# ATtiny10Thermometer.net
KiCad netlist of a schematic drawn in EAGLE
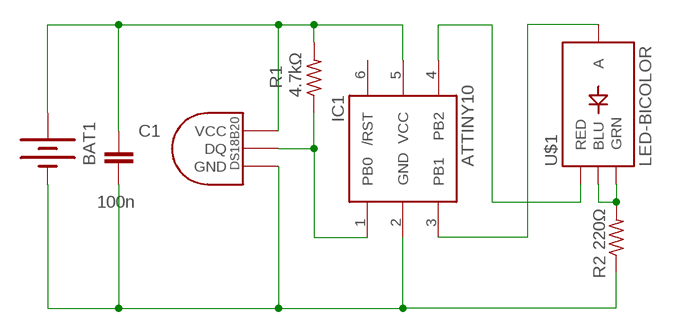
[diagram p0: schematic, sheet 1]

(export (version "E")
  (design (tool "Eeschema 10.0.6"))
  (components
    (comp (ref "BAT1")
      (value "BATTERY12MM")
      (footprint "eagle-import:BATTCON_12MM")
      (libsource (lib "eagle-import") (part "BATTERY12MM"))
    )
    (comp (ref "C1")
      (value "100n")
      (footprint "eagle-import:0603-CAP")
      (libsource (lib "eagle-import") (part "CAP0603-CAP"))
    )
    (comp (ref "IC1")
      (value "ATTINY10")
      (footprint "eagle-import:SOT23-6")
      (libsource (lib "eagle-import") (part "ATTINY10"))
    )
    (comp (ref "R1")
      (value "4.7kΩ")
      (footprint "eagle-import:R0805")
      (libsource (lib "eagle-import") (part "R-US_R0805"))
    )
    (comp (ref "R2")
      (value "220Ω")
      (footprint "eagle-import:R0805")
      (libsource (lib "eagle-import") (part "R-US_R0805"))
    )
    (comp (ref "U$1")
      (value "LED-BICOLOR")
      (footprint "eagle-import:LED-TRICOLOR-SMD")
      (libsource (lib "eagle-import") (part "LED-TRICOLOR"))
    )
    (comp (ref "U$2")
      (value "DS1820")
      (footprint "eagle-import:µSOP8")
      (libsource (lib "eagle-import") (part "DS1820"))
    )
  )
  (nets
    (net (code "1") (name "Net-(BAT1-+)") (class "Default")
      (node (ref "BAT1") (pin "PWR@1") (pinfunction "+_PWR@1") (pintype "power_in"))
      (node (ref "C1") (pin "1") (pinfunction "1_1") (pintype "passive"))
      (node (ref "IC1") (pin "5") (pinfunction "VCC_5") (pintype "power_in"))
      (node (ref "R1") (pin "2") (pinfunction "2_2") (pintype "passive"))
      (node (ref "U$2") (pin "8") (pinfunction "VCC_8") (pintype "power_in"))
    )
    (net (code "2") (name "Net-(BAT1--)") (class "Default")
      (node (ref "BAT1") (pin "GND") (pinfunction "-_GND") (pintype "power_in"))
      (node (ref "C1") (pin "2") (pinfunction "2_2") (pintype "passive"))
      (node (ref "IC1") (pin "2") (pinfunction "GND_2") (pintype "power_in"))
      (node (ref "R2") (pin "1") (pinfunction "1_1") (pintype "passive"))
      (node (ref "U$2") (pin "4") (pinfunction "GND_4") (pintype "power_in"))
    )
    (net (code "3") (name "Net-(IC1-PB0)") (class "Default")
      (node (ref "IC1") (pin "1") (pinfunction "PB0_1") (pintype "bidirectional"))
      (node (ref "R1") (pin "1") (pinfunction "1_1") (pintype "passive"))
      (node (ref "U$2") (pin "1") (pinfunction "DQ_1") (pintype "bidirectional"))
    )
    (net (code "4") (name "Net-(IC1-PB1)") (class "Default")
      (node (ref "IC1") (pin "3") (pinfunction "PB1_3") (pintype "bidirectional"))
      (node (ref "U$1") (pin "A") (pinfunction "A_A") (pintype "bidirectional"))
    )
    (net (code "5") (name "Net-(IC1-PB2)") (class "Default")
      (node (ref "IC1") (pin "4") (pinfunction "PB2_4") (pintype "bidirectional"))
      (node (ref "U$1") (pin "R") (pinfunction "RED_R") (pintype "bidirectional"))
    )
    (net (code "6") (name "Net-(U$1-BLU)") (class "Default")
      (node (ref "R2") (pin "2") (pinfunction "2_2") (pintype "passive"))
      (node (ref "U$1") (pin "B") (pinfunction "BLU_B") (pintype "bidirectional"))
      (node (ref "U$1") (pin "G") (pinfunction "GRN_G") (pintype "bidirectional"))
    )
    (net (code "7") (name "unconnected-(IC1-{slash}RST-Pad6)") (class "Default")
      (node (ref "IC1") (pin "6") (pinfunction "/RST_6") (pintype "bidirectional"))
    )
  )
)
